# Power_VtopControl.net
KiCad netlist of a schematic drawn in Altium Designer
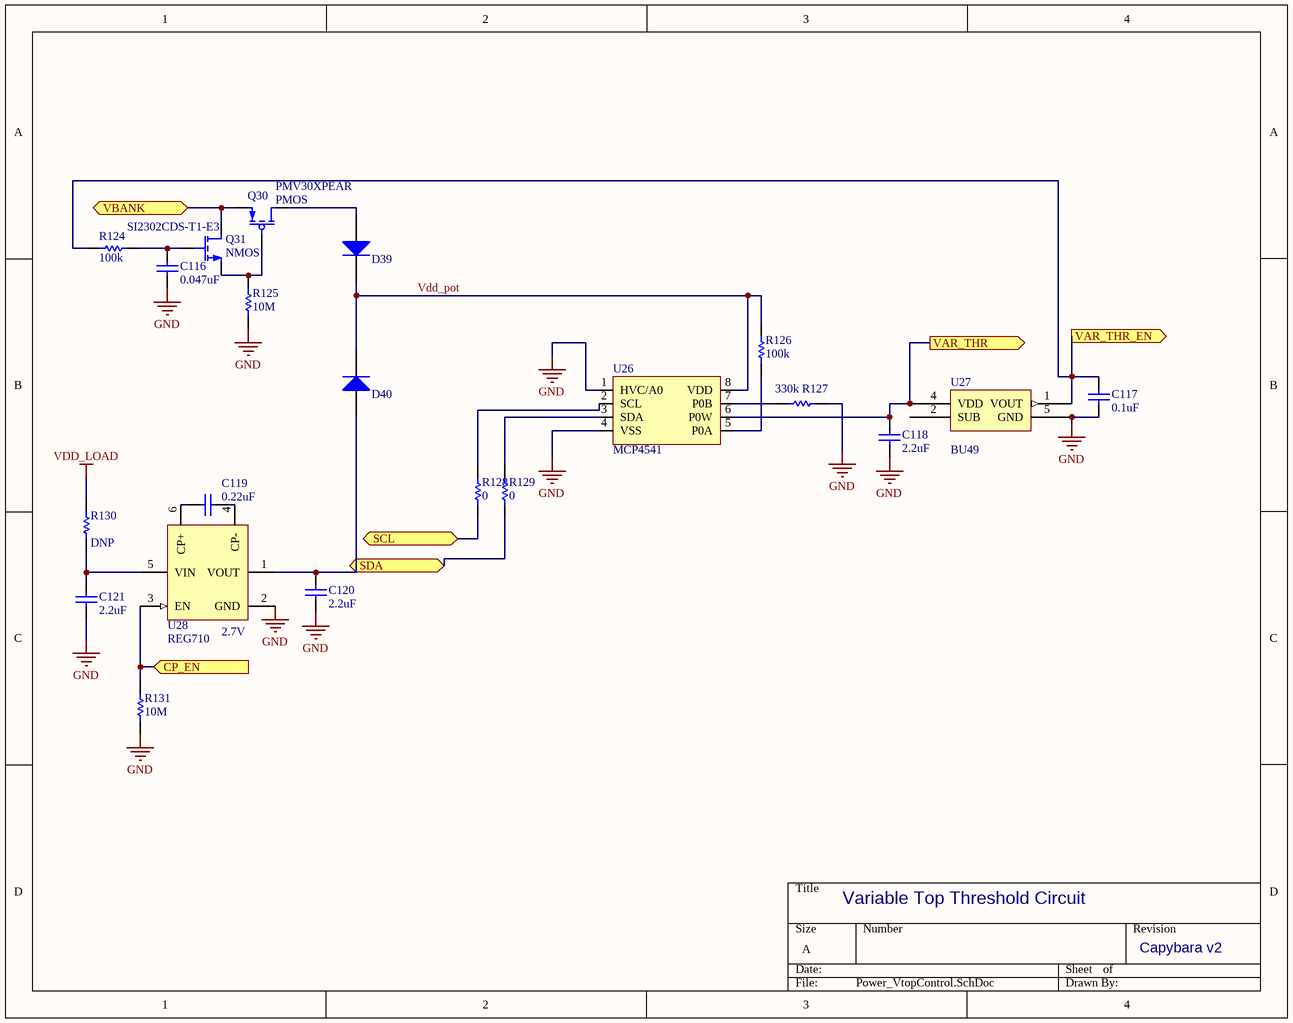
[diagram p0: Power_VtopControl.SchDoc]

(export (version "E")
  (design (tool "Eeschema 10.0.6"))
  (components
    (comp (ref "C116")
      (value "0.047uF")
      (footprint "0603")
      (description "Ceramic Capacitor (Surface Mount)")
      (fields
        (field (name "MANUFACTURER") "Murata Electronics North America")
        (field (name "MANUFACTURER PART NUMBER") "GRM188R71H473KA61D")
      )
      (libsource (lib "DRP_Basic_2014") (part "Cap"))
    )
    (comp (ref "C117")
      (value "0.1uF")
      (footprint "0603")
      (description "Ceramic Capacitor (Surface Mount)")
      (fields
        (field (name "MANUFACTURER") "Murata Electronics North America")
        (field (name "MANUFACTURER PART NUMBER") "GRM188R71C104KA01D")
      )
      (libsource (lib "DRP_Basic_2014") (part "Cap"))
    )
    (comp (ref "C118")
      (value "2.2uF")
      (footprint "0603")
      (description "Ceramic Capacitor (Surface Mount)")
      (fields
        (field (name "MANUFACTURER") "Murata Electronics North America")
        (field (name "MANUFACTURER PART NUMBER") "GRM188R61C225KE15D")
      )
      (libsource (lib "DRP_Basic_2014") (part "Cap"))
    )
    (comp (ref "C119")
      (value "0.22uF")
      (footprint "0603")
      (description "Ceramic Capacitor (Surface Mount)")
      (fields
        (field (name "MANUFACTURER") "Murata Electronics North America")
        (field (name "MANUFACTURER PART NUMBER") "GRM188R71E224KA88D")
      )
      (libsource (lib "DRP_Basic_2014") (part "Cap"))
    )
    (comp (ref "C120")
      (value "2.2uF")
      (footprint "0603")
      (description "Ceramic Capacitor (Surface Mount)")
      (fields
        (field (name "MANUFACTURER") "Murata Electronics North America")
        (field (name "MANUFACTURER PART NUMBER") "GRM188R61C225KE15D")
      )
      (libsource (lib "DRP_Basic_2014") (part "Cap"))
    )
    (comp (ref "C121")
      (value "2.2uF")
      (footprint "0603")
      (description "Ceramic Capacitor (Surface Mount)")
      (fields
        (field (name "MANUFACTURER") "Murata Electronics North America")
        (field (name "MANUFACTURER PART NUMBER") "GRM188R61C225KE15D")
      )
      (libsource (lib "DRP_Basic_2014") (part "Cap"))
    )
    (comp (ref "D39")
      (value "Diode")
      (footprint "SOD-523")
      (description "General Purpose Diode")
      (fields
        (field (name "MANUFACTURER") "Vishay Semiconductor")
        (field (name "MANUFACTURER PART NUMBER") "BAS40-02V-V-G-08")
      )
      (libsource (lib "DRP_Basic_2014") (part "Diode"))
    )
    (comp (ref "D40")
      (value "Diode")
      (footprint "SOD-523")
      (description "General Purpose Diode")
      (fields
        (field (name "MANUFACTURER") "Vishay Semiconductor")
        (field (name "MANUFACTURER PART NUMBER") "BAS40-02V-V-G-08")
      )
      (libsource (lib "DRP_Basic_2014") (part "Diode"))
    )
    (comp (ref "Q30")
      (value "PMOS")
      (footprint "SOT23 - N")
      (description "P-Channel MOSFET")
      (fields
        (field (name "DIGI-KEY PART NUMBER") "1727-2531-1-ND")
        (field (name "MANUFACTURER PART NUMBER") "PMV30XPEAR")
        (field (name "MANUFACTURER") "Nexperia")
      )
      (libsource (lib "DRP_Basic_2014") (part "MOSFET-P"))
    )
    (comp (ref "Q31")
      (value "NMOS")
      (footprint "SOT23 - N")
      (description "N-Channel MOSFET")
      (fields
        (field (name "DIGI-KEY PART NUMBER") "SI2302CDS-T1-E3CT-ND")
        (field (name "MANUFACTURER PART NUMBER") "SI2302CDS-T1-E3")
        (field (name "MANUFACTURER") "Vishay Siliconix")
      )
      (libsource (lib "DRP_Basic_2014") (part "MOSFET-N"))
    )
    (comp (ref "R124")
      (value "100k")
      (footprint "0603")
      (description "Chip Resistor (Surface Mount)")
      (fields
        (field (name "MANUFACTURER") "Yageo")
        (field (name "MANUFACTURER PART NUMBER") "RT0603FRE07100KL")
      )
      (libsource (lib "DRP_Basic_2014") (part "Res"))
    )
    (comp (ref "R125")
      (value "10M")
      (footprint "0603")
      (description "Chip Resistor (Surface Mount)")
      (fields
        (field (name "MANUFACTURER") "Yageo")
        (field (name "MANUFACTURER PART NUMBER") "RC0603JR-0710ML")
      )
      (libsource (lib "DRP_Basic_2014") (part "Res"))
    )
    (comp (ref "R126")
      (value "100k")
      (footprint "0603")
      (description "Chip Resistor (Surface Mount)")
      (fields
        (field (name "MANUFACTURER") "Yageo")
        (field (name "MANUFACTURER PART NUMBER") "RT0603FRE07100KL")
      )
      (libsource (lib "DRP_Basic_2014") (part "Res"))
    )
    (comp (ref "R127")
      (value "330k")
      (footprint "0603")
      (description "Chip Resistor (Surface Mount)")
      (fields
        (field (name "MANUFACTURER") "Yageo")
        (field (name "MANUFACTURER PART NUMBER") "RC0603FR-07330KL")
      )
      (libsource (lib "DRP_Basic_2014") (part "Res"))
    )
    (comp (ref "R128")
      (value "0")
      (footprint "0603")
      (description "Chip Resistor (Surface Mount)")
      (fields
        (field (name "MANUFACTURER") "Yageo")
        (field (name "MANUFACTURER PART NUMBER") "RC0603JR-070RL")
      )
      (libsource (lib "DRP_Basic_2014") (part "Res"))
    )
    (comp (ref "R129")
      (value "0")
      (footprint "0603")
      (description "Chip Resistor (Surface Mount)")
      (fields
        (field (name "MANUFACTURER") "Yageo")
        (field (name "MANUFACTURER PART NUMBER") "RC0603JR-070RL")
      )
      (libsource (lib "DRP_Basic_2014") (part "Res"))
    )
    (comp (ref "R130")
      (value "DNP")
      (footprint "0603")
      (description "Chip Resistor (Surface Mount)")
      (fields (field (name "MANUFACTURER") "Generic Chip Res (TBD)") (field (name "Comment") "Res"))
      (libsource (lib "DRP_Basic_2014") (part "Res"))
    )
    (comp (ref "R131")
      (value "10M")
      (footprint "0603")
      (description "Chip Resistor (Surface Mount)")
      (fields
        (field (name "MANUFACTURER") "Yageo")
        (field (name "MANUFACTURER PART NUMBER") "RC0603JR-0710ML")
      )
      (libsource (lib "DRP_Basic_2014") (part "Res"))
    )
    (comp (ref "U26")
      (value "MCP4541")
      (footprint "MSOP8")
      (fields
        (field (name "DIGI-KEY PART NUMBER") "MCP4541-104E/MS-ND")
        (field (name "DISTRIBUTOR PART NUMBER") "579-MCP4541-104E/MS")
        (field (name "MANUFACTURER") "Microchip")
      )
      (libsource (lib "Sprite") (part "MCP4541"))
    )
    (comp (ref "U27")
      (value "BU49")
      (footprint "SOP4")
      (description "IC DETECTOR CMOS")
      (fields
        (field (name "NAME") "BU49")
        (field (name "DIGI-KEY PART NUMBER") "BU4917F-TR-ND")
        (field (name "DISTRIBUTOR PART NUMBER") "BU4917F-TR")
      )
      (libsource (lib "Sprite") (part "BU49"))
    )
    (comp (ref "U28")
      (value "REG710")
      (footprint "SOT23-6")
      (fields
        (field (name "ALTIUM_VALUE") "2.7V")
        (field (name "DIGI-KEY PART NUMBER") "296-12134-1-ND")
        (field (name "DISTRIBUTOR PART NUMBER") "595-REG710NA-2.7/250")
        (field (name "MANUFACTURER") "Texas Instruments")
      )
      (libsource (lib "Sprite") (part "REG710"))
    )
  )
  (nets
    (net (code "1") (name "/CP_EN") (class "Default")
      (node (ref "R131") (pin "2") (pinfunction "2_2") (pintype "passive"))
      (node (ref "U28") (pin "3") (pinfunction "EN_3") (pintype "input"))
    )
    (net (code "2") (name "/SCL") (class "Default")
      (node (ref "R128") (pin "1") (pinfunction "1_1") (pintype "passive"))
    )
    (net (code "3") (name "/SDA") (class "Default")
      (node (ref "R129") (pin "1") (pinfunction "1_1") (pintype "passive"))
    )
    (net (code "4") (name "/VAR_THR") (class "Default")
      (node (ref "C118") (pin "2") (pinfunction "2_2") (pintype "passive"))
      (node (ref "U26") (pin "6") (pinfunction "P0W_6") (pintype "passive"))
      (node (ref "U27") (pin "4") (pinfunction "VDD_4") (pintype "power_in"))
    )
    (net (code "5") (name "/VAR_THR_EN") (class "Default")
      (node (ref "C117") (pin "2") (pinfunction "2_2") (pintype "passive"))
      (node (ref "R124") (pin "1") (pinfunction "1_1") (pintype "passive"))
      (node (ref "U27") (pin "1") (pinfunction "VOUT_1") (pintype "output"))
    )
    (net (code "6") (name "/VBANK") (class "Default")
      (node (ref "Q30") (pin "2") (pinfunction "S_2") (pintype "passive"))
      (node (ref "Q31") (pin "3") (pinfunction "D_3") (pintype "passive"))
    )
    (net (code "7") (name "/Vdd_pot") (class "Default")
      (node (ref "D39") (pin "2") (pinfunction "C_2") (pintype "passive"))
      (node (ref "D40") (pin "2") (pinfunction "C_2") (pintype "passive"))
      (node (ref "R126") (pin "2") (pinfunction "2_2") (pintype "passive"))
      (node (ref "U26") (pin "8") (pinfunction "VDD_8") (pintype "passive"))
    )
    (net (code "8") (name "GND") (class "Default")
      (node (ref "C116") (pin "1") (pinfunction "1_1") (pintype "passive"))
      (node (ref "C117") (pin "1") (pinfunction "1_1") (pintype "passive"))
      (node (ref "C118") (pin "1") (pinfunction "1_1") (pintype "passive"))
      (node (ref "C120") (pin "1") (pinfunction "1_1") (pintype "passive"))
      (node (ref "C121") (pin "1") (pinfunction "1_1") (pintype "passive"))
      (node (ref "R125") (pin "1") (pinfunction "1_1") (pintype "passive"))
      (node (ref "R127") (pin "1") (pinfunction "1_1") (pintype "passive"))
      (node (ref "R131") (pin "1") (pinfunction "1_1") (pintype "passive"))
      (node (ref "U26") (pin "1") (pinfunction "HVC/A0_1") (pintype "passive"))
      (node (ref "U26") (pin "4") (pinfunction "VSS_4") (pintype "passive"))
      (node (ref "U27") (pin "5") (pinfunction "GND_5") (pintype "power_in"))
      (node (ref "U28") (pin "2") (pinfunction "GND_2") (pintype "power_in"))
    )
    (net (code "9") (name "Net-(D39-A)") (class "Default")
      (node (ref "D39") (pin "1") (pinfunction "A_1") (pintype "passive"))
      (node (ref "Q30") (pin "3") (pinfunction "D_3") (pintype "passive"))
    )
    (net (code "10") (name "Net-(D40-A)") (class "Default")
      (node (ref "C120") (pin "2") (pinfunction "2_2") (pintype "passive"))
      (node (ref "D40") (pin "1") (pinfunction "A_1") (pintype "passive"))
      (node (ref "U28") (pin "1") (pinfunction "VOUT_1") (pintype "passive"))
    )
    (net (code "11") (name "Net-(Q30-G)") (class "Default")
      (node (ref "Q30") (pin "1") (pinfunction "G_1") (pintype "passive"))
      (node (ref "Q31") (pin "2") (pinfunction "S_2") (pintype "passive"))
      (node (ref "R125") (pin "2") (pinfunction "2_2") (pintype "passive"))
    )
    (net (code "12") (name "Net-(Q31-G)") (class "Default")
      (node (ref "C116") (pin "2") (pinfunction "2_2") (pintype "passive"))
      (node (ref "Q31") (pin "1") (pinfunction "G_1") (pintype "passive"))
      (node (ref "R124") (pin "2") (pinfunction "2_2") (pintype "passive"))
    )
    (net (code "13") (name "Net-(U26-P0A)") (class "Default")
      (node (ref "R126") (pin "1") (pinfunction "1_1") (pintype "passive"))
      (node (ref "U26") (pin "5") (pinfunction "P0A_5") (pintype "passive"))
    )
    (net (code "14") (name "Net-(U26-P0B)") (class "Default")
      (node (ref "R127") (pin "2") (pinfunction "2_2") (pintype "passive"))
      (node (ref "U26") (pin "7") (pinfunction "P0B_7") (pintype "passive"))
    )
    (net (code "15") (name "Net-(U26-SCL)") (class "Default")
      (node (ref "R128") (pin "2") (pinfunction "2_2") (pintype "passive"))
      (node (ref "U26") (pin "2") (pinfunction "SCL_2") (pintype "passive"))
    )
    (net (code "16") (name "Net-(U26-SDA)") (class "Default")
      (node (ref "R129") (pin "2") (pinfunction "2_2") (pintype "passive"))
      (node (ref "U26") (pin "3") (pinfunction "SDA_3") (pintype "passive"))
    )
    (net (code "17") (name "Net-(U28-CP+)") (class "Default")
      (node (ref "C119") (pin "2") (pinfunction "2_2") (pintype "passive"))
      (node (ref "U28") (pin "6") (pinfunction "CP+_6") (pintype "passive"))
    )
    (net (code "18") (name "Net-(U28-CP-)") (class "Default")
      (node (ref "C119") (pin "1") (pinfunction "1_1") (pintype "passive"))
      (node (ref "U28") (pin "4") (pinfunction "CP-_4") (pintype "passive"))
    )
    (net (code "19") (name "Net-(U28-VIN)") (class "Default")
      (node (ref "C121") (pin "2") (pinfunction "2_2") (pintype "passive"))
      (node (ref "R130") (pin "2") (pinfunction "2_2") (pintype "passive"))
      (node (ref "U28") (pin "5") (pinfunction "VIN_5") (pintype "power_in"))
    )
    (net (code "20") (name "VDD_LOAD") (class "Default")
      (node (ref "R130") (pin "1") (pinfunction "1_1") (pintype "passive"))
    )
    (net (code "21") (name "unconnected-(U27-SUB-Pad2)") (class "Default")
      (node (ref "U27") (pin "2") (pinfunction "SUB_2") (pintype "passive"))
    )
  )
)
